# FPGA_I2C.net
KiCad netlist of a schematic drawn in Altium Designer
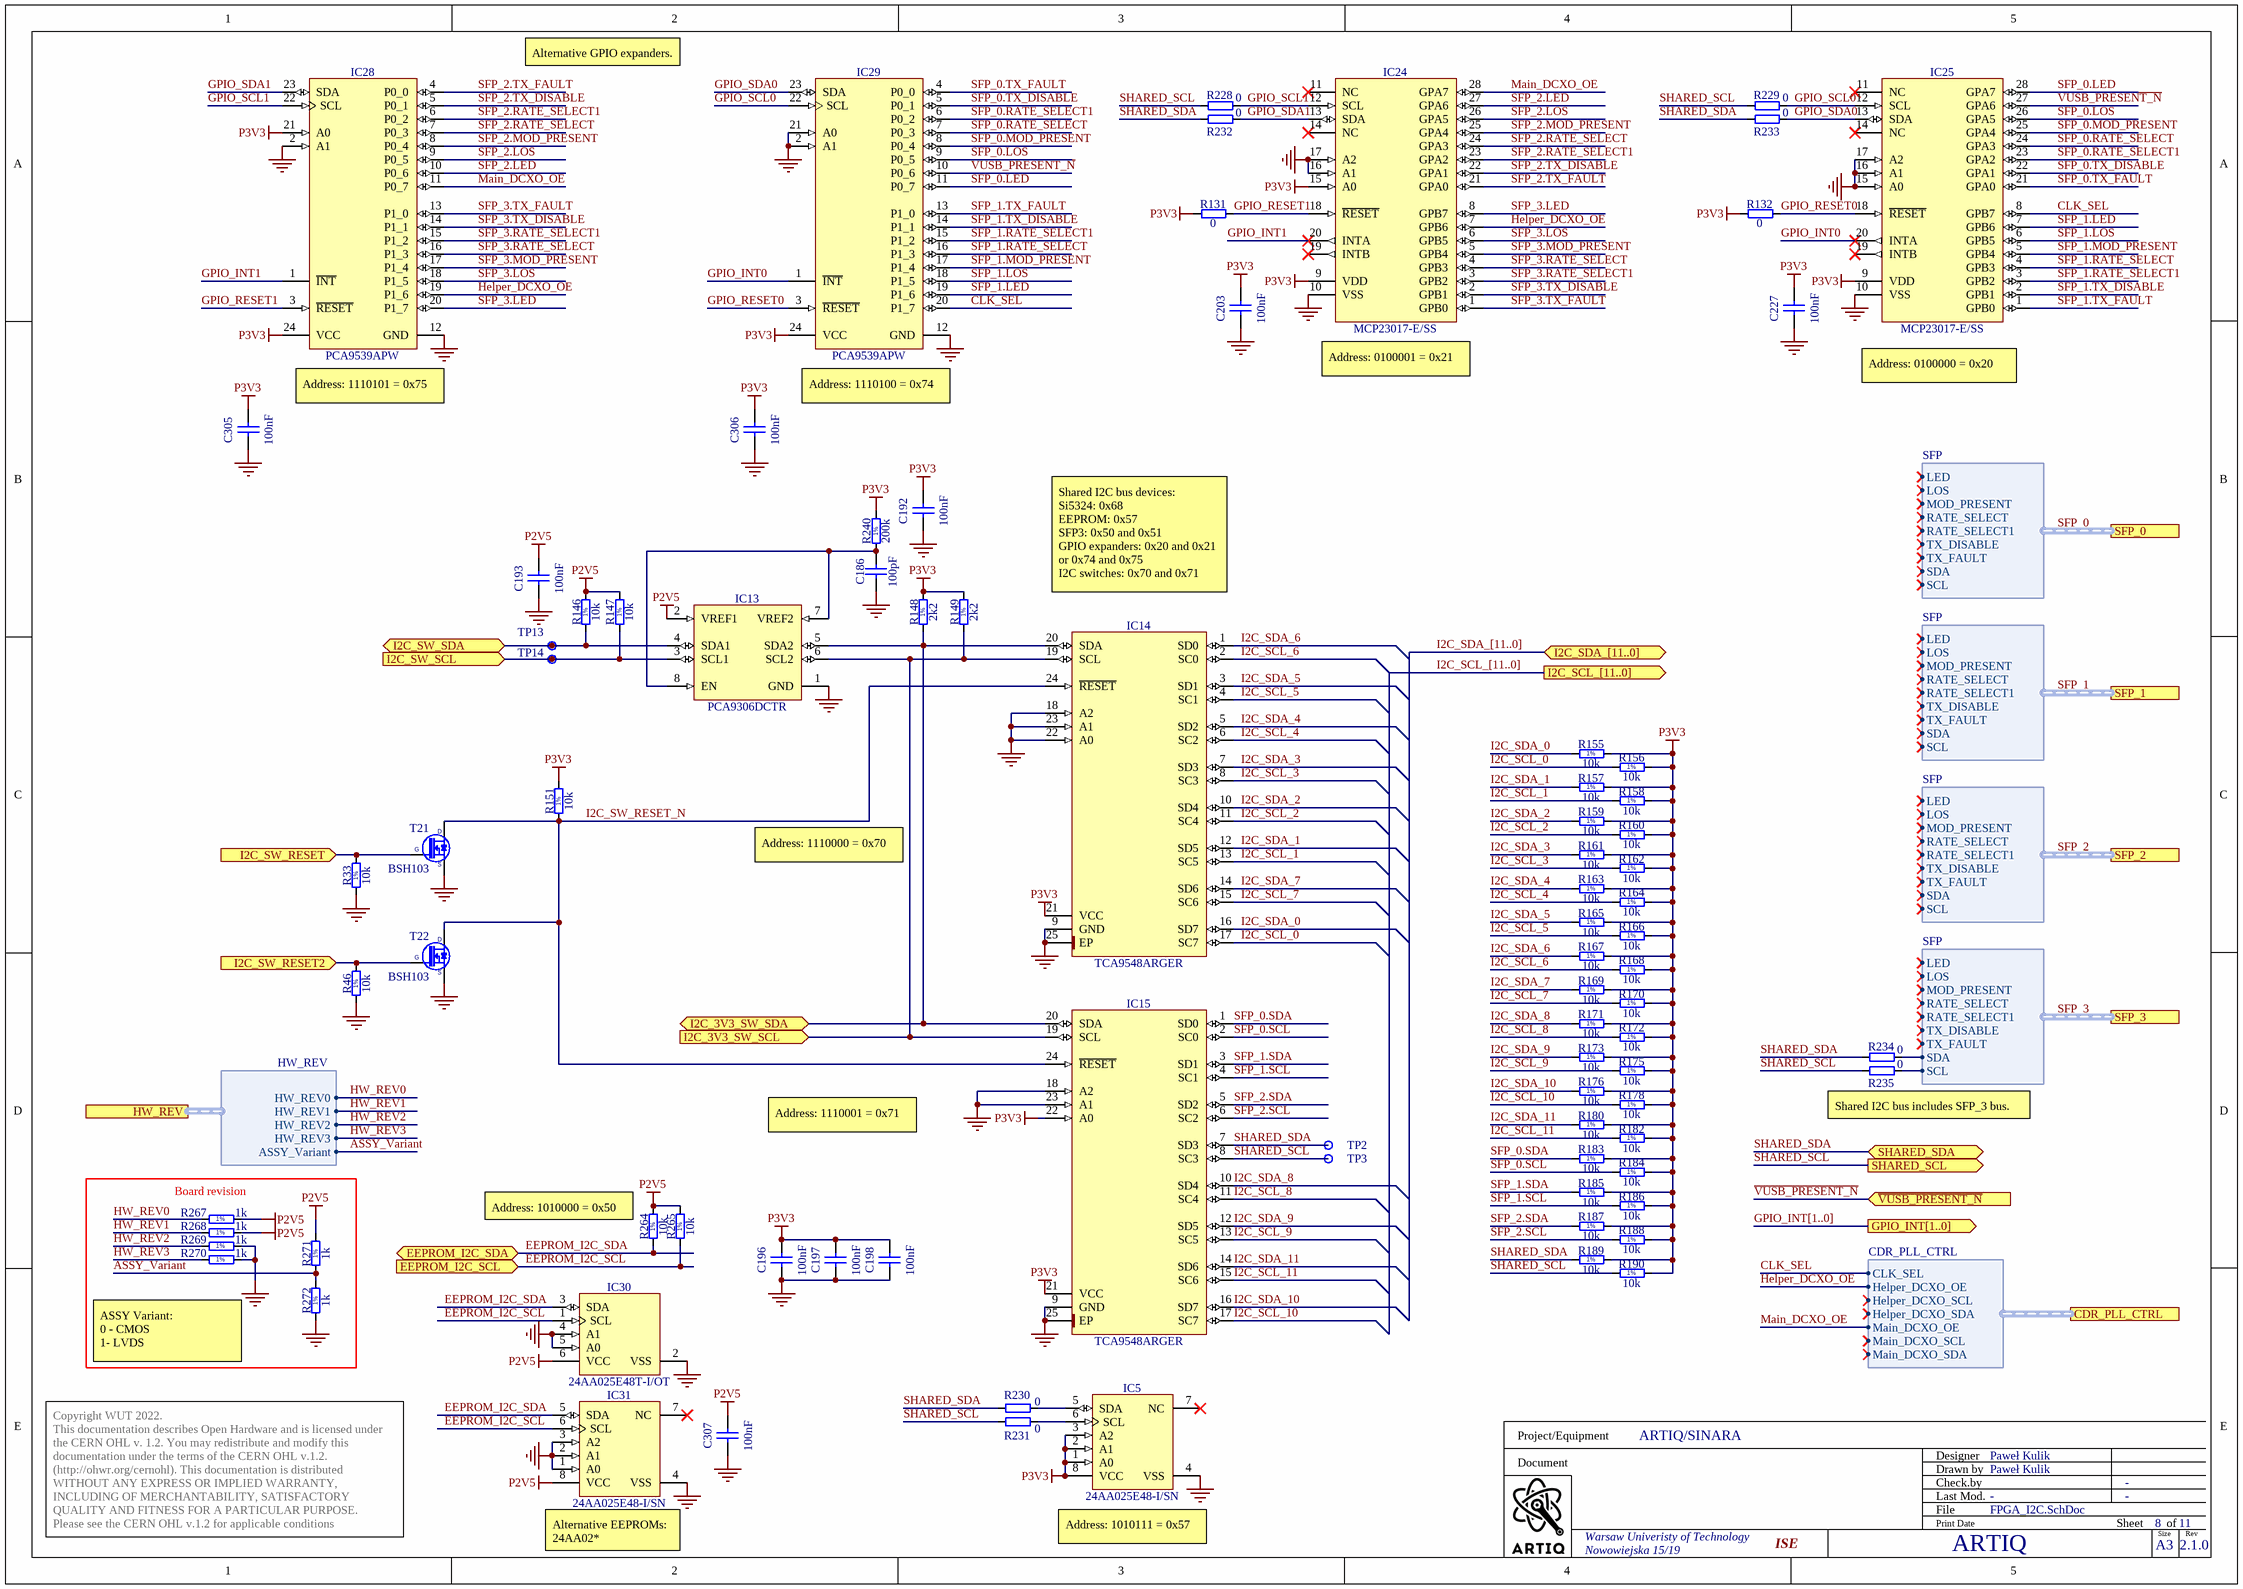
[diagram p0: FPGA_I2C.SchDoc]

(export (version "E")
  (design (tool "Eeschema 10.0.6"))
  (components
    (comp (ref "C186")
      (value "100pF")
      (footprint "CAPC1005X55N")
      (description "Non-polarised capacitor")
      (fields
        (field (name "PART NUMBER") "CC0402_100PF_50V_5%_C0G")
        (field (name "VOLTAGE") "50V")
        (field (name "AUTHOR") "CERN DEM JLC")
      )
      (libsource (lib "Capacitors") (part "Capacitor - non polarized"))
    )
    (comp (ref "C192")
      (value "100nF")
      (footprint "CAPC0603X33N")
      (description "Non-polarised capacitor")
      (fields
        (field (name "PART NUMBER") "CC0201_100NF_6.3V_10%_X5R")
        (field (name "VOLTAGE") "6.3V")
        (field (name "AUTHOR") "CERN DEM JLC")
      )
      (libsource (lib "Capacitors") (part "Capacitor - non polarized"))
    )
    (comp (ref "C193")
      (value "100nF")
      (footprint "CAPC0603X33N")
      (description "Non-polarised capacitor")
      (fields
        (field (name "PART NUMBER") "CC0201_100NF_6.3V_10%_X5R")
        (field (name "VOLTAGE") "6.3V")
        (field (name "AUTHOR") "CERN DEM JLC")
      )
      (libsource (lib "Capacitors") (part "Capacitor - non polarized"))
    )
    (comp (ref "C196")
      (value "100nF")
      (footprint "CAPC0603X33N")
      (description "Non-polarised capacitor")
      (fields
        (field (name "PART NUMBER") "CC0201_100NF_6.3V_10%_X5R")
        (field (name "VOLTAGE") "6.3V")
        (field (name "AUTHOR") "CERN DEM JLC")
      )
      (libsource (lib "Capacitors") (part "Capacitor - non polarized"))
    )
    (comp (ref "C197")
      (value "100nF")
      (footprint "CAPC0603X33N")
      (description "Non-polarised capacitor")
      (fields
        (field (name "PART NUMBER") "CC0201_100NF_6.3V_10%_X5R")
        (field (name "VOLTAGE") "6.3V")
        (field (name "AUTHOR") "CERN DEM JLC")
      )
      (libsource (lib "Capacitors") (part "Capacitor - non polarized"))
    )
    (comp (ref "C198")
      (value "100nF")
      (footprint "CAPC0603X33N")
      (description "Non-polarised capacitor")
      (fields
        (field (name "PART NUMBER") "CC0201_100NF_6.3V_10%_X5R")
        (field (name "VOLTAGE") "6.3V")
        (field (name "AUTHOR") "CERN DEM JLC")
      )
      (libsource (lib "Capacitors") (part "Capacitor - non polarized"))
    )
    (comp (ref "C203")
      (value "100nF")
      (footprint "CAPC0603X33N")
      (description "Non-polarised capacitor")
      (fields
        (field (name "PART NUMBER") "CC0201_100NF_6.3V_10%_X5R")
        (field (name "VOLTAGE") "6.3V")
        (field (name "AUTHOR") "CERN DEM JLC")
      )
      (libsource (lib "Capacitors") (part "Capacitor - non polarized"))
    )
    (comp (ref "C227")
      (value "100nF")
      (footprint "CAPC0603X33N")
      (description "Non-polarised capacitor")
      (fields
        (field (name "PART NUMBER") "CC0201_100NF_6.3V_10%_X5R")
        (field (name "VOLTAGE") "6.3V")
        (field (name "AUTHOR") "CERN DEM JLC")
      )
      (libsource (lib "Capacitors") (part "Capacitor - non polarized"))
    )
    (comp (ref "C305")
      (value "100nF")
      (footprint "CAPC0603X33N")
      (description "Non-polarised capacitor")
      (fields
        (field (name "PART NUMBER") "CC0201_100NF_6.3V_10%_X5R")
        (field (name "VOLTAGE") "6.3V")
        (field (name "AUTHOR") "CERN DEM JLC")
      )
      (libsource (lib "Capacitors") (part "Capacitor - non polarized"))
    )
    (comp (ref "C306")
      (value "100nF")
      (footprint "CAPC0603X33N")
      (description "Non-polarised capacitor")
      (fields
        (field (name "PART NUMBER") "CC0201_100NF_6.3V_10%_X5R")
        (field (name "VOLTAGE") "6.3V")
        (field (name "AUTHOR") "CERN DEM JLC")
      )
      (libsource (lib "Capacitors") (part "Capacitor - non polarized"))
    )
    (comp (ref "C307")
      (value "100nF")
      (footprint "CAPC1005X55N")
      (description "Non-polarised capacitor")
      (fields
        (field (name "PART NUMBER") "CC0402_100NF_16V_10%_X5R")
        (field (name "VOLTAGE") "16V")
        (field (name "AUTHOR") "CERN DEM JLC")
      )
      (libsource (lib "Capacitors") (part "Capacitor - non polarized"))
    )
    (comp (ref "IC5")
      (value "24AA025E48-I/SN")
      (footprint "SOIC127P600X175-8N")
      (description "1.7V-5.5V, 2K I2C™ Serial EEPROMs with EUI-48™ Node Identity")
      (fields (field (name "MANUFACTURER") "MICROCHIP TECHNOLOGY") (field (name "AUTHOR") "CERN DEM MR"))
      (libsource (lib "ICs And Semiconductors") (part "24AA025E48-I/SN"))
    )
    (comp (ref "IC13")
      (value "PCA9306DCTR")
      (footprint "SOP65P400X130-8N")
      (description "Dual Bidirectional I2C Bus And SMBus Voltage-Level Translator")
      (fields (field (name "MANUFACTURER") "TEXAS INSTRUMENTS") (field (name "AUTHOR") "CERN DEM JLC"))
      (libsource (lib "ICs And Semiconductors") (part "PCA9306D"))
    )
    (comp (ref "IC14")
      (value "TCA9548ARGER")
      (footprint "QFN50P400X400X100-25N-S220")
      (description "Low Voltage 8-Channel I2C Switch With Reset")
      (fields (field (name "MANUFACTURER") "TEXAS INSTRUMENTS") (field (name "AUTHOR") "CERN DEM JLC"))
      (libsource (lib "ICs And Semiconductors") (part "TCA9548ARGER"))
    )
    (comp (ref "IC15")
      (value "TCA9548ARGER")
      (footprint "QFN50P400X400X100-25N-S220")
      (description "Low Voltage 8-Channel I2C Switch With Reset")
      (fields (field (name "MANUFACTURER") "TEXAS INSTRUMENTS") (field (name "AUTHOR") "CERN DEM JLC"))
      (libsource (lib "ICs And Semiconductors") (part "TCA9548ARGER"))
    )
    (comp (ref "IC24")
      (value "MCP23017-E/SS")
      (footprint "SOP65P780X200-28N")
      (description "16-bit I/O Port Expander With Serial Interface")
      (fields (field (name "MANUFACTURER") "MICROCHIP TECHNOLOGY") (field (name "AUTHOR") "CERN DEM JLC"))
      (libsource (lib "ICs And Semiconductors") (part "MCP23017-E/SS"))
    )
    (comp (ref "IC25")
      (value "MCP23017-E/SS")
      (footprint "SOP65P780X200-28N")
      (description "16-bit I/O Port Expander With Serial Interface")
      (fields (field (name "MANUFACTURER") "MICROCHIP TECHNOLOGY") (field (name "AUTHOR") "CERN DEM JLC"))
      (libsource (lib "ICs And Semiconductors") (part "MCP23017-E/SS"))
    )
    (comp (ref "IC28")
      (value "PCA9539APW")
      (footprint "SOP65P640X110-24N")
      (description "Low-Voltage 16-Bit I2C-Bus I/O Port with Interrupt and Reset")
      (fields (field (name "MANUFACTURER") "NXP SEMICONDUCTORS") (field (name "AUTHOR") "CERN DEM JMW"))
      (libsource (lib "ICs And Semiconductors") (part "PCA9539APW"))
    )
    (comp (ref "IC29")
      (value "PCA9539APW")
      (footprint "SOP65P640X110-24N")
      (description "Low-Voltage 16-Bit I2C-Bus I/O Port with Interrupt and Reset")
      (fields (field (name "MANUFACTURER") "NXP SEMICONDUCTORS") (field (name "AUTHOR") "CERN DEM JMW"))
      (libsource (lib "ICs And Semiconductors") (part "PCA9539APW"))
    )
    (comp (ref "IC30")
      (value "24AA025E48T-I/OT")
      (footprint "SOT95P280X145-6N")
      (description "1.7V-5.5V, 2K I2C Serial EEPROM With EUI-48 Node Identity")
      (fields (field (name "MANUFACTURER") "MICROCHIP TECHNOLOGY") (field (name "AUTHOR") "CERN DEM BC"))
      (libsource (lib "ICs And Semiconductors") (part "24AA025E48T-I/OT"))
    )
    (comp (ref "IC31")
      (value "24AA025E48-I/SN")
      (footprint "SOIC127P600X175-8N")
      (description "1.7V-5.5V, 2K I2C™ Serial EEPROMs with EUI-48™ Node Identity")
      (fields (field (name "MANUFACTURER") "MICROCHIP TECHNOLOGY") (field (name "AUTHOR") "CERN DEM MR"))
      (libsource (lib "ICs And Semiconductors") (part "24AA025E48-I/SN"))
    )
    (comp (ref "R33")
      (value "10k")
      (footprint "RESC1005X40N")
      (description "Resistor - 1%")
      (fields
        (field (name "PART NUMBER") "R0402_10K_1%_0.0625W_100PPM")
        (field (name "POWER") "0.0625W")
        (field (name "AUTHOR") "CERN DEM JLC")
      )
      (libsource (lib "Resistors") (part "Resistor - 1%"))
    )
    (comp (ref "R46")
      (value "10k")
      (footprint "RESC1005X40N")
      (description "Resistor - 1%")
      (fields
        (field (name "PART NUMBER") "R0402_10K_1%_0.0625W_100PPM")
        (field (name "POWER") "0.0625W")
        (field (name "AUTHOR") "CERN DEM JLC")
      )
      (libsource (lib "Resistors") (part "Resistor - 1%"))
    )
    (comp (ref "R131")
      (value "0")
      (footprint "RESC1005X40N")
      (description "Resistor")
      (fields
        (field (name "PART NUMBER") "R0402_0R_JUMPER")
        (field (name "MANUFACTURER") "GENERIC")
        (field (name "AUTHOR") "CERN DEM JLC")
      )
      (libsource (lib "Resistors") (part "Resistor"))
    )
    (comp (ref "R132")
      (value "0")
      (footprint "RESC1005X40N")
      (description "Resistor")
      (fields
        (field (name "PART NUMBER") "R0402_0R_JUMPER")
        (field (name "MANUFACTURER") "GENERIC")
        (field (name "AUTHOR") "CERN DEM JLC")
      )
      (libsource (lib "Resistors") (part "Resistor"))
    )
    (comp (ref "R146")
      (value "10k")
      (footprint "RESC1005X40N")
      (description "Resistor - 1%")
      (fields
        (field (name "PART NUMBER") "R0402_10K_1%_0.0625W_100PPM")
        (field (name "POWER") "0.0625W")
        (field (name "AUTHOR") "CERN DEM JLC")
      )
      (libsource (lib "Resistors") (part "Resistor - 1%"))
    )
    (comp (ref "R147")
      (value "10k")
      (footprint "RESC1005X40N")
      (description "Resistor - 1%")
      (fields
        (field (name "PART NUMBER") "R0402_10K_1%_0.0625W_100PPM")
        (field (name "POWER") "0.0625W")
        (field (name "AUTHOR") "CERN DEM JLC")
      )
      (libsource (lib "Resistors") (part "Resistor - 1%"))
    )
    (comp (ref "R148")
      (value "2k2")
      (footprint "RESC1005X40N")
      (description "Resistor - 1%")
      (fields
        (field (name "PART NUMBER") "R0402_2K2_1%_0.0625W_100PPM")
        (field (name "POWER") "0.0625W")
        (field (name "AUTHOR") "CERN DEM JLC")
      )
      (libsource (lib "Resistors") (part "Resistor - 1%"))
    )
    (comp (ref "R149")
      (value "2k2")
      (footprint "RESC1005X40N")
      (description "Resistor - 1%")
      (fields
        (field (name "PART NUMBER") "R0402_2K2_1%_0.0625W_100PPM")
        (field (name "POWER") "0.0625W")
        (field (name "AUTHOR") "CERN DEM JLC")
      )
      (libsource (lib "Resistors") (part "Resistor - 1%"))
    )
    (comp (ref "R151")
      (value "10k")
      (footprint "RESC1005X40N")
      (description "Resistor - 1%")
      (fields
        (field (name "PART NUMBER") "R0402_10K_1%_0.0625W_100PPM")
        (field (name "POWER") "0.0625W")
        (field (name "AUTHOR") "CERN DEM JLC")
      )
      (libsource (lib "Resistors") (part "Resistor - 1%"))
    )
    (comp (ref "R155")
      (value "10k")
      (footprint "RESC1005X40N")
      (description "Resistor - 1%")
      (fields
        (field (name "PART NUMBER") "R0402_10K_1%_0.0625W_100PPM")
        (field (name "POWER") "0.0625W")
        (field (name "AUTHOR") "CERN DEM JLC")
      )
      (libsource (lib "Resistors") (part "Resistor - 1%"))
    )
    (comp (ref "R156")
      (value "10k")
      (footprint "RESC1005X40N")
      (description "Resistor - 1%")
      (fields
        (field (name "PART NUMBER") "R0402_10K_1%_0.0625W_100PPM")
        (field (name "POWER") "0.0625W")
        (field (name "AUTHOR") "CERN DEM JLC")
      )
      (libsource (lib "Resistors") (part "Resistor - 1%"))
    )
    (comp (ref "R157")
      (value "10k")
      (footprint "RESC1005X40N")
      (description "Resistor - 1%")
      (fields
        (field (name "PART NUMBER") "R0402_10K_1%_0.0625W_100PPM")
        (field (name "POWER") "0.0625W")
        (field (name "AUTHOR") "CERN DEM JLC")
      )
      (libsource (lib "Resistors") (part "Resistor - 1%"))
    )
    (comp (ref "R158")
      (value "10k")
      (footprint "RESC1005X40N")
      (description "Resistor - 1%")
      (fields
        (field (name "PART NUMBER") "R0402_10K_1%_0.0625W_100PPM")
        (field (name "POWER") "0.0625W")
        (field (name "AUTHOR") "CERN DEM JLC")
      )
      (libsource (lib "Resistors") (part "Resistor - 1%"))
    )
    (comp (ref "R159")
      (value "10k")
      (footprint "RESC1005X40N")
      (description "Resistor - 1%")
      (fields
        (field (name "PART NUMBER") "R0402_10K_1%_0.0625W_100PPM")
        (field (name "POWER") "0.0625W")
        (field (name "AUTHOR") "CERN DEM JLC")
      )
      (libsource (lib "Resistors") (part "Resistor - 1%"))
    )
    (comp (ref "R160")
      (value "10k")
      (footprint "RESC1005X40N")
      (description "Resistor - 1%")
      (fields
        (field (name "PART NUMBER") "R0402_10K_1%_0.0625W_100PPM")
        (field (name "POWER") "0.0625W")
        (field (name "AUTHOR") "CERN DEM JLC")
      )
      (libsource (lib "Resistors") (part "Resistor - 1%"))
    )
    (comp (ref "R161")
      (value "10k")
      (footprint "RESC1005X40N")
      (description "Resistor - 1%")
      (fields
        (field (name "PART NUMBER") "R0402_10K_1%_0.0625W_100PPM")
        (field (name "POWER") "0.0625W")
        (field (name "AUTHOR") "CERN DEM JLC")
      )
      (libsource (lib "Resistors") (part "Resistor - 1%"))
    )
    (comp (ref "R162")
      (value "10k")
      (footprint "RESC1005X40N")
      (description "Resistor - 1%")
      (fields
        (field (name "PART NUMBER") "R0402_10K_1%_0.0625W_100PPM")
        (field (name "POWER") "0.0625W")
        (field (name "AUTHOR") "CERN DEM JLC")
      )
      (libsource (lib "Resistors") (part "Resistor - 1%"))
    )
    (comp (ref "R163")
      (value "10k")
      (footprint "RESC1005X40N")
      (description "Resistor - 1%")
      (fields
        (field (name "PART NUMBER") "R0402_10K_1%_0.0625W_100PPM")
        (field (name "POWER") "0.0625W")
        (field (name "AUTHOR") "CERN DEM JLC")
      )
      (libsource (lib "Resistors") (part "Resistor - 1%"))
    )
    (comp (ref "R164")
      (value "10k")
      (footprint "RESC1005X40N")
      (description "Resistor - 1%")
      (fields
        (field (name "PART NUMBER") "R0402_10K_1%_0.0625W_100PPM")
        (field (name "POWER") "0.0625W")
        (field (name "AUTHOR") "CERN DEM JLC")
      )
      (libsource (lib "Resistors") (part "Resistor - 1%"))
    )
    (comp (ref "R165")
      (value "10k")
      (footprint "RESC1005X40N")
      (description "Resistor - 1%")
      (fields
        (field (name "PART NUMBER") "R0402_10K_1%_0.0625W_100PPM")
        (field (name "POWER") "0.0625W")
        (field (name "AUTHOR") "CERN DEM JLC")
      )
      (libsource (lib "Resistors") (part "Resistor - 1%"))
    )
    (comp (ref "R166")
      (value "10k")
      (footprint "RESC1005X40N")
      (description "Resistor - 1%")
      (fields
        (field (name "PART NUMBER") "R0402_10K_1%_0.0625W_100PPM")
        (field (name "POWER") "0.0625W")
        (field (name "AUTHOR") "CERN DEM JLC")
      )
      (libsource (lib "Resistors") (part "Resistor - 1%"))
    )
    (comp (ref "R167")
      (value "10k")
      (footprint "RESC1005X40N")
      (description "Resistor - 1%")
      (fields
        (field (name "PART NUMBER") "R0402_10K_1%_0.0625W_100PPM")
        (field (name "POWER") "0.0625W")
        (field (name "AUTHOR") "CERN DEM JLC")
      )
      (libsource (lib "Resistors") (part "Resistor - 1%"))
    )
    (comp (ref "R168")
      (value "10k")
      (footprint "RESC1005X40N")
      (description "Resistor - 1%")
      (fields
        (field (name "PART NUMBER") "R0402_10K_1%_0.0625W_100PPM")
        (field (name "POWER") "0.0625W")
        (field (name "AUTHOR") "CERN DEM JLC")
      )
      (libsource (lib "Resistors") (part "Resistor - 1%"))
    )
    (comp (ref "R169")
      (value "10k")
      (footprint "RESC1005X40N")
      (description "Resistor - 1%")
      (fields
        (field (name "PART NUMBER") "R0402_10K_1%_0.0625W_100PPM")
        (field (name "POWER") "0.0625W")
        (field (name "AUTHOR") "CERN DEM JLC")
      )
      (libsource (lib "Resistors") (part "Resistor - 1%"))
    )
    (comp (ref "R170")
      (value "10k")
      (footprint "RESC1005X40N")
      (description "Resistor - 1%")
      (fields
        (field (name "PART NUMBER") "R0402_10K_1%_0.0625W_100PPM")
        (field (name "POWER") "0.0625W")
        (field (name "AUTHOR") "CERN DEM JLC")
      )
      (libsource (lib "Resistors") (part "Resistor - 1%"))
    )
    (comp (ref "R171")
      (value "10k")
      (footprint "RESC1005X40N")
      (description "Resistor - 1%")
      (fields
        (field (name "PART NUMBER") "R0402_10K_1%_0.0625W_100PPM")
        (field (name "POWER") "0.0625W")
        (field (name "AUTHOR") "CERN DEM JLC")
      )
      (libsource (lib "Resistors") (part "Resistor - 1%"))
    )
    (comp (ref "R172")
      (value "10k")
      (footprint "RESC1005X40N")
      (description "Resistor - 1%")
      (fields
        (field (name "PART NUMBER") "R0402_10K_1%_0.0625W_100PPM")
        (field (name "POWER") "0.0625W")
        (field (name "AUTHOR") "CERN DEM JLC")
      )
      (libsource (lib "Resistors") (part "Resistor - 1%"))
    )
    (comp (ref "R173")
      (value "10k")
      (footprint "RESC1005X40N")
      (description "Resistor - 1%")
      (fields
        (field (name "PART NUMBER") "R0402_10K_1%_0.0625W_100PPM")
        (field (name "POWER") "0.0625W")
        (field (name "AUTHOR") "CERN DEM JLC")
      )
      (libsource (lib "Resistors") (part "Resistor - 1%"))
    )
    (comp (ref "R175")
      (value "10k")
      (footprint "RESC1005X40N")
      (description "Resistor - 1%")
      (fields
        (field (name "PART NUMBER") "R0402_10K_1%_0.0625W_100PPM")
        (field (name "POWER") "0.0625W")
        (field (name "AUTHOR") "CERN DEM JLC")
      )
      (libsource (lib "Resistors") (part "Resistor - 1%"))
    )
    (comp (ref "R176")
      (value "10k")
      (footprint "RESC1005X40N")
      (description "Resistor - 1%")
      (fields
        (field (name "PART NUMBER") "R0402_10K_1%_0.0625W_100PPM")
        (field (name "POWER") "0.0625W")
        (field (name "AUTHOR") "CERN DEM JLC")
      )
      (libsource (lib "Resistors") (part "Resistor - 1%"))
    )
    (comp (ref "R178")
      (value "10k")
      (footprint "RESC1005X40N")
      (description "Resistor - 1%")
      (fields
        (field (name "PART NUMBER") "R0402_10K_1%_0.0625W_100PPM")
        (field (name "POWER") "0.0625W")
        (field (name "AUTHOR") "CERN DEM JLC")
      )
      (libsource (lib "Resistors") (part "Resistor - 1%"))
    )
    (comp (ref "R180")
      (value "10k")
      (footprint "RESC1005X40N")
      (description "Resistor - 1%")
      (fields
        (field (name "PART NUMBER") "R0402_10K_1%_0.0625W_100PPM")
        (field (name "POWER") "0.0625W")
        (field (name "AUTHOR") "CERN DEM JLC")
      )
      (libsource (lib "Resistors") (part "Resistor - 1%"))
    )
    (comp (ref "R182")
      (value "10k")
      (footprint "RESC1005X40N")
      (description "Resistor - 1%")
      (fields
        (field (name "PART NUMBER") "R0402_10K_1%_0.0625W_100PPM")
        (field (name "POWER") "0.0625W")
        (field (name "AUTHOR") "CERN DEM JLC")
      )
      (libsource (lib "Resistors") (part "Resistor - 1%"))
    )
    (comp (ref "R183")
      (value "10k")
      (footprint "RESC1005X40N")
      (description "Resistor - 1%")
      (fields
        (field (name "PART NUMBER") "R0402_10K_1%_0.0625W_100PPM")
        (field (name "POWER") "0.0625W")
        (field (name "AUTHOR") "CERN DEM JLC")
      )
      (libsource (lib "Resistors") (part "Resistor - 1%"))
    )
    (comp (ref "R184")
      (value "10k")
      (footprint "RESC1005X40N")
      (description "Resistor - 1%")
      (fields
        (field (name "PART NUMBER") "R0402_10K_1%_0.0625W_100PPM")
        (field (name "POWER") "0.0625W")
        (field (name "AUTHOR") "CERN DEM JLC")
      )
      (libsource (lib "Resistors") (part "Resistor - 1%"))
    )
    (comp (ref "R185")
      (value "10k")
      (footprint "RESC1005X40N")
      (description "Resistor - 1%")
      (fields
        (field (name "PART NUMBER") "R0402_10K_1%_0.0625W_100PPM")
        (field (name "POWER") "0.0625W")
        (field (name "AUTHOR") "CERN DEM JLC")
      )
      (libsource (lib "Resistors") (part "Resistor - 1%"))
    )
    (comp (ref "R186")
      (value "10k")
      (footprint "RESC1005X40N")
      (description "Resistor - 1%")
      (fields
        (field (name "PART NUMBER") "R0402_10K_1%_0.0625W_100PPM")
        (field (name "POWER") "0.0625W")
        (field (name "AUTHOR") "CERN DEM JLC")
      )
      (libsource (lib "Resistors") (part "Resistor - 1%"))
    )
    (comp (ref "R187")
      (value "10k")
      (footprint "RESC1005X40N")
      (description "Resistor - 1%")
      (fields
        (field (name "PART NUMBER") "R0402_10K_1%_0.0625W_100PPM")
        (field (name "POWER") "0.0625W")
        (field (name "AUTHOR") "CERN DEM JLC")
      )
      (libsource (lib "Resistors") (part "Resistor - 1%"))
    )
    (comp (ref "R188")
      (value "10k")
      (footprint "RESC1005X40N")
      (description "Resistor - 1%")
      (fields
        (field (name "PART NUMBER") "R0402_10K_1%_0.0625W_100PPM")
        (field (name "POWER") "0.0625W")
        (field (name "AUTHOR") "CERN DEM JLC")
      )
      (libsource (lib "Resistors") (part "Resistor - 1%"))
    )
    (comp (ref "R189")
      (value "10k")
      (footprint "RESC1005X40N")
      (description "Resistor - 1%")
      (fields
        (field (name "PART NUMBER") "R0402_10K_1%_0.0625W_100PPM")
        (field (name "POWER") "0.0625W")
        (field (name "AUTHOR") "CERN DEM JLC")
      )
      (libsource (lib "Resistors") (part "Resistor - 1%"))
    )
    (comp (ref "R190")
      (value "10k")
      (footprint "RESC1005X40N")
      (description "Resistor - 1%")
      (fields
        (field (name "PART NUMBER") "R0402_10K_1%_0.0625W_100PPM")
        (field (name "POWER") "0.0625W")
        (field (name "AUTHOR") "CERN DEM JLC")
      )
      (libsource (lib "Resistors") (part "Resistor - 1%"))
    )
    (comp (ref "R228")
      (value "0")
      (footprint "RESC1005X40N")
      (description "Resistor")
      (fields
        (field (name "PART NUMBER") "R0402_0R_JUMPER")
        (field (name "MANUFACTURER") "GENERIC")
        (field (name "AUTHOR") "CERN DEM JLC")
      )
      (libsource (lib "Resistors") (part "Resistor"))
    )
    (comp (ref "R229")
      (value "0")
      (footprint "RESC1005X40N")
      (description "Resistor")
      (fields
        (field (name "PART NUMBER") "R0402_0R_JUMPER")
        (field (name "MANUFACTURER") "GENERIC")
        (field (name "AUTHOR") "CERN DEM JLC")
      )
      (libsource (lib "Resistors") (part "Resistor"))
    )
    (comp (ref "R230")
      (value "0")
      (footprint "RESC1005X40N")
      (description "Resistor")
      (fields
        (field (name "PART NUMBER") "R0402_0R_JUMPER")
        (field (name "MANUFACTURER") "GENERIC")
        (field (name "AUTHOR") "CERN DEM JLC")
      )
      (libsource (lib "Resistors") (part "Resistor"))
    )
    (comp (ref "R231")
      (value "0")
      (footprint "RESC1005X40N")
      (description "Resistor")
      (fields
        (field (name "PART NUMBER") "R0402_0R_JUMPER")
        (field (name "MANUFACTURER") "GENERIC")
        (field (name "AUTHOR") "CERN DEM JLC")
      )
      (libsource (lib "Resistors") (part "Resistor"))
    )
    (comp (ref "R232")
      (value "0")
      (footprint "RESC1005X40N")
      (description "Resistor")
      (fields
        (field (name "PART NUMBER") "R0402_0R_JUMPER")
        (field (name "MANUFACTURER") "GENERIC")
        (field (name "AUTHOR") "CERN DEM JLC")
      )
      (libsource (lib "Resistors") (part "Resistor"))
    )
    (comp (ref "R233")
      (value "0")
      (footprint "RESC1005X40N")
      (description "Resistor")
      (fields
        (field (name "PART NUMBER") "R0402_0R_JUMPER")
        (field (name "MANUFACTURER") "GENERIC")
        (field (name "AUTHOR") "CERN DEM JLC")
      )
      (libsource (lib "Resistors") (part "Resistor"))
    )
    (comp (ref "R234")
      (value "0")
      (footprint "RESC1005X40N")
      (description "Resistor")
      (fields
        (field (name "PART NUMBER") "R0402_0R_JUMPER")
        (field (name "MANUFACTURER") "GENERIC")
        (field (name "AUTHOR") "CERN DEM JLC")
      )
      (libsource (lib "Resistors") (part "Resistor"))
    )
    (comp (ref "R235")
      (value "0")
      (footprint "RESC1005X40N")
      (description "Resistor")
      (fields
        (field (name "PART NUMBER") "R0402_0R_JUMPER")
        (field (name "MANUFACTURER") "GENERIC")
        (field (name "AUTHOR") "CERN DEM JLC")
      )
      (libsource (lib "Resistors") (part "Resistor"))
    )
    (comp (ref "R240")
      (value "200k")
      (footprint "RESC1005X40N")
      (description "Resistor - 1%")
      (fields
        (field (name "PART NUMBER") "R0402_200K_1%_0.0625W_100PPM")
        (field (name "POWER") "0.0625W")
        (field (name "AUTHOR") "CERN DEM JLC")
      )
      (libsource (lib "Resistors") (part "Resistor - 1%"))
    )
    (comp (ref "R264")
      (value "10k")
      (footprint "RESC1005X40N")
      (description "Resistor - 1%")
      (fields
        (field (name "PART NUMBER") "R0402_10K_1%_0.0625W_100PPM")
        (field (name "POWER") "0.0625W")
        (field (name "AUTHOR") "CERN DEM JLC")
      )
      (libsource (lib "Resistors") (part "Resistor - 1%"))
    )
    (comp (ref "R265")
      (value "10k")
      (footprint "RESC1005X40N")
      (description "Resistor - 1%")
      (fields
        (field (name "PART NUMBER") "R0402_10K_1%_0.0625W_100PPM")
        (field (name "POWER") "0.0625W")
        (field (name "AUTHOR") "CERN DEM JLC")
      )
      (libsource (lib "Resistors") (part "Resistor - 1%"))
    )
    (comp (ref "R267")
      (value "1k")
      (footprint "RESC1005X40N")
      (description "Resistor - 1%")
      (fields
        (field (name "PART NUMBER") "R0402_1K_1%_0.0625W_100PPM")
        (field (name "POWER") "0.0625W")
        (field (name "AUTHOR") "CERN DEM JLC")
      )
      (libsource (lib "Resistors") (part "Resistor - 1%"))
    )
    (comp (ref "R268")
      (value "1k")
      (footprint "RESC1005X40N")
      (description "Resistor - 1%")
      (fields
        (field (name "PART NUMBER") "R0402_1K_1%_0.0625W_100PPM")
        (field (name "POWER") "0.0625W")
        (field (name "AUTHOR") "CERN DEM JLC")
      )
      (libsource (lib "Resistors") (part "Resistor - 1%"))
    )
    (comp (ref "R269")
      (value "1k")
      (footprint "RESC1005X40N")
      (description "Resistor - 1%")
      (fields
        (field (name "PART NUMBER") "R0402_1K_1%_0.0625W_100PPM")
        (field (name "POWER") "0.0625W")
        (field (name "AUTHOR") "CERN DEM JLC")
      )
      (libsource (lib "Resistors") (part "Resistor - 1%"))
    )
    (comp (ref "R270")
      (value "1k")
      (footprint "RESC1005X40N")
      (description "Resistor - 1%")
      (fields
        (field (name "PART NUMBER") "R0402_1K_1%_0.0625W_100PPM")
        (field (name "POWER") "0.0625W")
        (field (name "AUTHOR") "CERN DEM JLC")
      )
      (libsource (lib "Resistors") (part "Resistor - 1%"))
    )
    (comp (ref "R271")
      (value "1k")
      (footprint "RESC1005X40N")
      (description "Resistor - 1%")
      (fields
        (field (name "PART NUMBER") "R0402_1K_1%_0.0625W_100PPM")
        (field (name "POWER") "0.0625W")
        (field (name "AUTHOR") "CERN DEM JLC")
      )
      (libsource (lib "Resistors") (part "Resistor - 1%"))
    )
    (comp (ref "R272")
      (value "1k")
      (footprint "RESC1005X40N")
      (description "Resistor - 1%")
      (fields
        (field (name "PART NUMBER") "R0402_1K_1%_0.0625W_100PPM")
        (field (name "POWER") "0.0625W")
        (field (name "AUTHOR") "CERN DEM JLC")
      )
      (libsource (lib "Resistors") (part "Resistor - 1%"))
    )
    (comp (ref "T21")
      (value "BSH103")
      (footprint "SOT95P230X110-3N")
      (description "N-CHANNEL MOSFET WITH DIODE")
      (fields (field (name "MANUFACTURER") "NEXPERIA") (field (name "AUTHOR") "CERN DEM JLC"))
      (libsource (lib "ICs And Semiconductors") (part "N-MOSFET-D 1G 2S 3D"))
    )
    (comp (ref "T22")
      (value "BSH103")
      (footprint "SOT95P230X110-3N")
      (description "N-CHANNEL MOSFET WITH DIODE")
      (fields (field (name "MANUFACTURER") "NEXPERIA") (field (name "AUTHOR") "CERN DEM JLC"))
      (libsource (lib "ICs And Semiconductors") (part "N-MOSFET-D 1G 2S 3D"))
    )
    (comp (ref "TP2")
      (value "Si5324 I2C SDA")
      (footprint "TPS127")
      (description "Test Point")
      (fields (field (name "PART NUMBER") "SMD_PAD_1.27X1.27MM") (field (name "AUTHOR") "CERN DEM JLC"))
      (libsource (lib "Eletro-mechanical") (part "Test Point"))
    )
    (comp (ref "TP3")
      (value "Si5324 I2C SCL")
      (footprint "TPS127")
      (description "Test Point")
      (fields (field (name "PART NUMBER") "SMD_PAD_1.27X1.27MM") (field (name "AUTHOR") "CERN DEM JLC"))
      (libsource (lib "Eletro-mechanical") (part "Test Point"))
    )
    (comp (ref "TP13")
      (value "I2C SW SDA")
      (footprint "TPS127")
      (description "Test Point")
      (fields (field (name "PART NUMBER") "SMD_PAD_1.27X1.27MM") (field (name "AUTHOR") "CERN DEM JLC"))
      (libsource (lib "Eletro-mechanical") (part "Test Point"))
    )
    (comp (ref "TP14")
      (value "I2C SW SCL")
      (footprint "TPS127")
      (description "Test Point")
      (fields (field (name "PART NUMBER") "SMD_PAD_1.27X1.27MM") (field (name "AUTHOR") "CERN DEM JLC"))
      (libsource (lib "Eletro-mechanical") (part "Test Point"))
    )
  )
  (nets
    (net (code "7") (name "/ASSY_Variant") (class "Default")
      (node (ref "R271") (pin "1") (pinfunction "1_1") (pintype "passive"))
      (node (ref "R272") (pin "2") (pinfunction "2_2") (pintype "passive"))
    )
    (net (code "8") (name "/CLK_SEL") (class "Default")
      (node (ref "IC25") (pin "8") (pinfunction "GPB7_8") (pintype "bidirectional"))
      (node (ref "IC29") (pin "20") (pinfunction "P1_7_20") (pintype "bidirectional"))
    )
    (net (code "9") (name "/EEPROM_I2C_SCL") (class "Default")
      (node (ref "IC30") (pin "1") (pinfunction "SCL_1") (pintype "input"))
      (node (ref "IC31") (pin "6") (pinfunction "SCL_6") (pintype "input"))
      (node (ref "R265") (pin "1") (pinfunction "1_1") (pintype "passive"))
    )
    (net (code "10") (name "/EEPROM_I2C_SDA") (class "Default")
      (node (ref "IC30") (pin "3") (pinfunction "SDA_3") (pintype "bidirectional"))
      (node (ref "IC31") (pin "5") (pinfunction "SDA_5") (pintype "bidirectional"))
      (node (ref "R264") (pin "1") (pinfunction "1_1") (pintype "passive"))
    )
    (net (code "11") (name "/GPIO_INT0") (class "Default")
      (node (ref "IC25") (pin "20") (pinfunction "INTA_20") (pintype "output"))
      (node (ref "IC29") (pin "1") (pinfunction "~{INT}_1") (pintype "open_collector"))
    )
    (net (code "12") (name "/GPIO_INT1") (class "Default")
      (node (ref "IC24") (pin "20") (pinfunction "INTA_20") (pintype "output"))
      (node (ref "IC28") (pin "1") (pinfunction "~{INT}_1") (pintype "open_collector"))
    )
    (net (code "14") (name "/GPIO_RESET0") (class "Default")
      (node (ref "IC25") (pin "18") (pinfunction "~{RESET}_18") (pintype "input"))
      (node (ref "IC29") (pin "3") (pinfunction "~{RESET}_3") (pintype "input"))
      (node (ref "R132") (pin "2") (pinfunction "2_2") (pintype "passive"))
    )
    (net (code "15") (name "/GPIO_RESET1") (class "Default")
      (node (ref "IC24") (pin "18") (pinfunction "~{RESET}_18") (pintype "input"))
      (node (ref "IC28") (pin "3") (pinfunction "~{RESET}_3") (pintype "input"))
      (node (ref "R131") (pin "2") (pinfunction "2_2") (pintype "passive"))
    )
    (net (code "16") (name "/GPIO_SCL0") (class "Default")
      (node (ref "IC25") (pin "12") (pinfunction "SCL_12") (pintype "input"))
      (node (ref "IC29") (pin "22") (pinfunction "SCL_22") (pintype "input"))
      (node (ref "R229") (pin "2") (pinfunction "2_2") (pintype "passive"))
    )
    (net (code "17") (name "/GPIO_SCL1") (class "Default")
      (node (ref "IC24") (pin "12") (pinfunction "SCL_12") (pintype "input"))
      (node (ref "IC28") (pin "22") (pinfunction "SCL_22") (pintype "input"))
      (node (ref "R228") (pin "2") (pinfunction "2_2") (pintype "passive"))
    )
    (net (code "18") (name "/GPIO_SDA0") (class "Default")
      (node (ref "IC25") (pin "13") (pinfunction "SDA_13") (pintype "bidirectional"))
      (node (ref "IC29") (pin "23") (pinfunction "SDA_23") (pintype "bidirectional"))
      (node (ref "R233") (pin "2") (pinfunction "2_2") (pintype "passive"))
    )
    (net (code "19") (name "/GPIO_SDA1") (class "Default")
      (node (ref "IC24") (pin "13") (pinfunction "SDA_13") (pintype "bidirectional"))
      (node (ref "IC28") (pin "23") (pinfunction "SDA_23") (pintype "bidirectional"))
      (node (ref "R232") (pin "2") (pinfunction "2_2") (pintype "passive"))
    )
    (net (code "20") (name "/HW_REV0") (class "Default")
      (node (ref "R267") (pin "1") (pinfunction "1_1") (pintype "passive"))
    )
    (net (code "21") (name "/HW_REV1") (class "Default")
      (node (ref "R268") (pin "1") (pinfunction "1_1") (pintype "passive"))
    )
    (net (code "22") (name "/HW_REV2") (class "Default")
      (node (ref "R269") (pin "1") (pinfunction "1_1") (pintype "passive"))
    )
    (net (code "23") (name "/HW_REV3") (class "Default")
      (node (ref "R270") (pin "1") (pinfunction "1_1") (pintype "passive"))
    )
    (net (code "24") (name "/Helper_DCXO_OE") (class "Default")
      (node (ref "IC24") (pin "7") (pinfunction "GPB6_7") (pintype "bidirectional"))
      (node (ref "IC28") (pin "19") (pinfunction "P1_6_19") (pintype "bidirectional"))
    )
    (net (code "25") (name "/I2C_3V3_SW_SCL") (class "Default")
      (node (ref "IC13") (pin "6") (pinfunction "SCL2_6") (pintype "bidirectional"))
      (node (ref "IC14") (pin "19") (pinfunction "SCL_19") (pintype "bidirectional"))
      (node (ref "IC15") (pin "19") (pinfunction "SCL_19") (pintype "bidirectional"))
      (node (ref "R149") (pin "1") (pinfunction "1_1") (pintype "passive"))
    )
    (net (code "26") (name "/I2C_3V3_SW_SDA") (class "Default")
      (node (ref "IC13") (pin "5") (pinfunction "SDA2_5") (pintype "bidirectional"))
      (node (ref "IC14") (pin "20") (pinfunction "SDA_20") (pintype "bidirectional"))
      (node (ref "IC15") (pin "20") (pinfunction "SDA_20") (pintype "bidirectional"))
      (node (ref "R148") (pin "1") (pinfunction "1_1") (pintype "passive"))
    )
    (net (code "27") (name "/I2C_SCL_0") (class "Default")
      (node (ref "IC14") (pin "17") (pinfunction "SC7_17") (pintype "bidirectional"))
      (node (ref "R156") (pin "1") (pinfunction "1_1") (pintype "passive"))
    )
    (net (code "28") (name "/I2C_SCL_1") (class "Default")
      (node (ref "IC14") (pin "13") (pinfunction "SC5_13") (pintype "bidirectional"))
      (node (ref "R158") (pin "1") (pinfunction "1_1") (pintype "passive"))
    )
    (net (code "29") (name "/I2C_SCL_2") (class "Default")
      (node (ref "IC14") (pin "11") (pinfunction "SC4_11") (pintype "bidirectional"))
      (node (ref "R160") (pin "1") (pinfunction "1_1") (pintype "passive"))
    )
    (net (code "30") (name "/I2C_SCL_3") (class "Default")
      (node (ref "IC14") (pin "8") (pinfunction "SC3_8") (pintype "bidirectional"))
      (node (ref "R162") (pin "1") (pinfunction "1_1") (pintype "passive"))
    )
    (net (code "31") (name "/I2C_SCL_4") (class "Default")
      (node (ref "IC14") (pin "6") (pinfunction "SC2_6") (pintype "bidirectional"))
      (node (ref "R164") (pin "1") (pinfunction "1_1") (pintype "passive"))
    )
    (net (code "32") (name "/I2C_SCL_5") (class "Default")
      (node (ref "IC14") (pin "4") (pinfunction "SC1_4") (pintype "bidirectional"))
      (node (ref "R166") (pin "1") (pinfunction "1_1") (pintype "passive"))
    )
    (net (code "33") (name "/I2C_SCL_6") (class "Default")
      (node (ref "IC14") (pin "2") (pinfunction "SC0_2") (pintype "bidirectional"))
      (node (ref "R168") (pin "1") (pinfunction "1_1") (pintype "passive"))
    )
    (net (code "34") (name "/I2C_SCL_7") (class "Default")
      (node (ref "IC14") (pin "15") (pinfunction "SC6_15") (pintype "bidirectional"))
      (node (ref "R170") (pin "1") (pinfunction "1_1") (pintype "passive"))
    )
    (net (code "35") (name "/I2C_SCL_8") (class "Default")
      (node (ref "IC15") (pin "11") (pinfunction "SC4_11") (pintype "bidirectional"))
      (node (ref "R172") (pin "1") (pinfunction "1_1") (pintype "passive"))
    )
    (net (code "36") (name "/I2C_SCL_9") (class "Default")
      (node (ref "IC15") (pin "13") (pinfunction "SC5_13") (pintype "bidirectional"))
      (node (ref "R175") (pin "1") (pinfunction "1_1") (pintype "passive"))
    )
    (net (code "37") (name "/I2C_SCL_10") (class "Default")
      (node (ref "IC15") (pin "17") (pinfunction "SC7_17") (pintype "bidirectional"))
      (node (ref "R178") (pin "1") (pinfunction "1_1") (pintype "passive"))
    )
    (net (code "38") (name "/I2C_SCL_11") (class "Default")
      (node (ref "IC15") (pin "15") (pinfunction "SC6_15") (pintype "bidirectional"))
      (node (ref "R182") (pin "1") (pinfunction "1_1") (pintype "passive"))
    )
    (net (code "40") (name "/I2C_SDA_0") (class "Default")
      (node (ref "IC14") (pin "16") (pinfunction "SD7_16") (pintype "bidirectional"))
      (node (ref "R155") (pin "1") (pinfunction "1_1") (pintype "passive"))
    )
    (net (code "41") (name "/I2C_SDA_1") (class "Default")
      (node (ref "IC14") (pin "12") (pinfunction "SD5_12") (pintype "bidirectional"))
      (node (ref "R157") (pin "1") (pinfunction "1_1") (pintype "passive"))
    )
    (net (code "42") (name "/I2C_SDA_2") (class "Default")
      (node (ref "IC14") (pin "10") (pinfunction "SD4_10") (pintype "bidirectional"))
      (node (ref "R159") (pin "1") (pinfunction "1_1") (pintype "passive"))
    )
    (net (code "43") (name "/I2C_SDA_3") (class "Default")
      (node (ref "IC14") (pin "7") (pinfunction "SD3_7") (pintype "bidirectional"))
      (node (ref "R161") (pin "1") (pinfunction "1_1") (pintype "passive"))
    )
    (net (code "44") (name "/I2C_SDA_4") (class "Default")
      (node (ref "IC14") (pin "5") (pinfunction "SD2_5") (pintype "bidirectional"))
      (node (ref "R163") (pin "1") (pinfunction "1_1") (pintype "passive"))
    )
    (net (code "45") (name "/I2C_SDA_5") (class "Default")
      (node (ref "IC14") (pin "3") (pinfunction "SD1_3") (pintype "bidirectional"))
      (node (ref "R165") (pin "1") (pinfunction "1_1") (pintype "passive"))
    )
    (net (code "46") (name "/I2C_SDA_6") (class "Default")
      (node (ref "IC14") (pin "1") (pinfunction "SD0_1") (pintype "bidirectional"))
      (node (ref "R167") (pin "1") (pinfunction "1_1") (pintype "passive"))
    )
    (net (code "47") (name "/I2C_SDA_7") (class "Default")
      (node (ref "IC14") (pin "14") (pinfunction "SD6_14") (pintype "bidirectional"))
      (node (ref "R169") (pin "1") (pinfunction "1_1") (pintype "passive"))
    )
    (net (code "48") (name "/I2C_SDA_8") (class "Default")
      (node (ref "IC15") (pin "10") (pinfunction "SD4_10") (pintype "bidirectional"))
      (node (ref "R171") (pin "1") (pinfunction "1_1") (pintype "passive"))
    )
    (net (code "49") (name "/I2C_SDA_9") (class "Default")
      (node (ref "IC15") (pin "12") (pinfunction "SD5_12") (pintype "bidirectional"))
      (node (ref "R173") (pin "1") (pinfunction "1_1") (pintype "passive"))
    )
    (net (code "50") (name "/I2C_SDA_10") (class "Default")
      (node (ref "IC15") (pin "16") (pinfunction "SD7_16") (pintype "bidirectional"))
      (node (ref "R176") (pin "1") (pinfunction "1_1") (pintype "passive"))
    )
    (net (code "51") (name "/I2C_SDA_11") (class "Default")
      (node (ref "IC15") (pin "14") (pinfunction "SD6_14") (pintype "bidirectional"))
      (node (ref "R180") (pin "1") (pinfunction "1_1") (pintype "passive"))
    )
    (net (code "53") (name "/I2C_SW_RESET") (class "Default")
      (node (ref "R33") (pin "2") (pinfunction "2_2") (pintype "passive"))
      (node (ref "T21") (pin "1") (pinfunction "G_1") (pintype "passive"))
    )
    (net (code "54") (name "/I2C_SW_RESET2") (class "Default")
      (node (ref "R46") (pin "2") (pinfunction "2_2") (pintype "passive"))
      (node (ref "T22") (pin "1") (pinfunction "G_1") (pintype "passive"))
    )
    (net (code "55") (name "/I2C_SW_RESET_N") (class "Default")
      (node (ref "IC14") (pin "24") (pinfunction "~{RESET}_24") (pintype "input"))
      (node (ref "IC15") (pin "24") (pinfunction "~{RESET}_24") (pintype "input"))
      (node (ref "R151") (pin "1") (pinfunction "1_1") (pintype "passive"))
      (node (ref "T21") (pin "3") (pinfunction "D_3") (pintype "passive"))
      (node (ref "T22") (pin "3") (pinfunction "D_3") (pintype "passive"))
    )
    (net (code "56") (name "/I2C_SW_SCL") (class "Default")
      (node (ref "IC13") (pin "3") (pinfunction "SCL1_3") (pintype "bidirectional"))
      (node (ref "R147") (pin "1") (pinfunction "1_1") (pintype "passive"))
      (node (ref "TP14") (pin "1") (pinfunction "1_1") (pintype "bidirectional"))
    )
    (net (code "57") (name "/I2C_SW_SDA") (class "Default")
      (node (ref "IC13") (pin "4") (pinfunction "SDA1_4") (pintype "bidirectional"))
      (node (ref "R146") (pin "1") (pinfunction "1_1") (pintype "passive"))
      (node (ref "TP13") (pin "1") (pinfunction "1_1") (pintype "bidirectional"))
    )
    (net (code "58") (name "/Main_DCXO_OE") (class "Default")
      (node (ref "IC24") (pin "28") (pinfunction "GPA7_28") (pintype "bidirectional"))
      (node (ref "IC28") (pin "11") (pinfunction "P0_7_11") (pintype "bidirectional"))
    )
    (net (code "59") (name "/SFP_0.LED") (class "Default")
      (node (ref "IC25") (pin "28") (pinfunction "GPA7_28") (pintype "bidirectional"))
      (node (ref "IC29") (pin "11") (pinfunction "P0_7_11") (pintype "bidirectional"))
    )
    (net (code "60") (name "/SFP_0.LOS") (class "Default")
      (node (ref "IC25") (pin "26") (pinfunction "GPA5_26") (pintype "bidirectional"))
      (node (ref "IC29") (pin "9") (pinfunction "P0_5_9") (pintype "bidirectional"))
    )
    (net (code "61") (name "/SFP_0.MOD_PRESENT") (class "Default")
      (node (ref "IC25") (pin "25") (pinfunction "GPA4_25") (pintype "bidirectional"))
      (node (ref "IC29") (pin "8") (pinfunction "P0_4_8") (pintype "bidirectional"))
    )
    (net (code "62") (name "/SFP_0.RATE_SELECT") (class "Default")
      (node (ref "IC25") (pin "24") (pinfunction "GPA3_24") (pintype "bidirectional"))
      (node (ref "IC29") (pin "7") (pinfunction "P0_3_7") (pintype "bidirectional"))
    )
    (net (code "63") (name "/SFP_0.RATE_SELECT1") (class "Default")
      (node (ref "IC25") (pin "23") (pinfunction "GPA2_23") (pintype "bidirectional"))
      (node (ref "IC29") (pin "6") (pinfunction "P0_2_6") (pintype "bidirectional"))
    )
    (net (code "64") (name "/SFP_0.SCL") (class "Default")
      (node (ref "IC15") (pin "2") (pinfunction "SC0_2") (pintype "bidirectional"))
      (node (ref "R184") (pin "1") (pinfunction "1_1") (pintype "passive"))
    )
    (net (code "65") (name "/SFP_0.SDA") (class "Default")
      (node (ref "IC15") (pin "1") (pinfunction "SD0_1") (pintype "bidirectional"))
      (node (ref "R183") (pin "1") (pinfunction "1_1") (pintype "passive"))
    )
    (net (code "66") (name "/SFP_0.TX_DISABLE") (class "Default")
      (node (ref "IC25") (pin "22") (pinfunction "GPA1_22") (pintype "bidirectional"))
      (node (ref "IC29") (pin "5") (pinfunction "P0_1_5") (pintype "bidirectional"))
    )
    (net (code "67") (name "/SFP_0.TX_FAULT") (class "Default")
      (node (ref "IC25") (pin "21") (pinfunction "GPA0_21") (pintype "bidirectional"))
      (node (ref "IC29") (pin "4") (pinfunction "P0_0_4") (pintype "bidirectional"))
    )
    (net (code "69") (name "/SFP_1.LED") (class "Default")
      (node (ref "IC25") (pin "7") (pinfunction "GPB6_7") (pintype "bidirectional"))
      (node (ref "IC29") (pin "19") (pinfunction "P1_6_19") (pintype "bidirectional"))
    )
    (net (code "70") (name "/SFP_1.LOS") (class "Default")
      (node (ref "IC25") (pin "6") (pinfunction "GPB5_6") (pintype "bidirectional"))
      (node (ref "IC29") (pin "18") (pinfunction "P1_5_18") (pintype "bidirectional"))
    )
    (net (code "71") (name "/SFP_1.MOD_PRESENT") (class "Default")
      (node (ref "IC25") (pin "5") (pinfunction "GPB4_5") (pintype "bidirectional"))
      (node (ref "IC29") (pin "17") (pinfunction "P1_4_17") (pintype "bidirectional"))
    )
    (net (code "72") (name "/SFP_1.RATE_SELECT") (class "Default")
      (node (ref "IC25") (pin "4") (pinfunction "GPB3_4") (pintype "bidirectional"))
      (node (ref "IC29") (pin "16") (pinfunction "P1_3_16") (pintype "bidirectional"))
    )
    (net (code "73") (name "/SFP_1.RATE_SELECT1") (class "Default")
      (node (ref "IC25") (pin "3") (pinfunction "GPB2_3") (pintype "bidirectional"))
      (node (ref "IC29") (pin "15") (pinfunction "P1_2_15") (pintype "bidirectional"))
    )
    (net (code "74") (name "/SFP_1.SCL") (class "Default")
      (node (ref "IC15") (pin "4") (pinfunction "SC1_4") (pintype "bidirectional"))
      (node (ref "R186") (pin "1") (pinfunction "1_1") (pintype "passive"))
    )
    (net (code "75") (name "/SFP_1.SDA") (class "Default")
      (node (ref "IC15") (pin "3") (pinfunction "SD1_3") (pintype "bidirectional"))
      (node (ref "R185") (pin "1") (pinfunction "1_1") (pintype "passive"))
    )
    (net (code "76") (name "/SFP_1.TX_DISABLE") (class "Default")
      (node (ref "IC25") (pin "2") (pinfunction "GPB1_2") (pintype "bidirectional"))
      (node (ref "IC29") (pin "14") (pinfunction "P1_1_14") (pintype "bidirectional"))
    )
    (net (code "77") (name "/SFP_1.TX_FAULT") (class "Default")
      (node (ref "IC25") (pin "1") (pinfunction "GPB0_1") (pintype "bidirectional"))
      (node (ref "IC29") (pin "13") (pinfunction "P1_0_13") (pintype "bidirectional"))
    )
    (net (code "79") (name "/SFP_2.LED") (class "Default")
      (node (ref "IC24") (pin "27") (pinfunction "GPA6_27") (pintype "bidirectional"))
      (node (ref "IC28") (pin "10") (pinfunction "P0_6_10") (pintype "bidirectional"))
    )
    (net (code "80") (name "/SFP_2.LOS") (class "Default")
      (node (ref "IC24") (pin "26") (pinfunction "GPA5_26") (pintype "bidirectional"))
      (node (ref "IC28") (pin "9") (pinfunction "P0_5_9") (pintype "bidirectional"))
    )
    (net (code "81") (name "/SFP_2.MOD_PRESENT") (class "Default")
      (node (ref "IC24") (pin "25") (pinfunction "GPA4_25") (pintype "bidirectional"))
      (node (ref "IC28") (pin "8") (pinfunction "P0_4_8") (pintype "bidirectional"))
    )
    (net (code "82") (name "/SFP_2.RATE_SELECT") (class "Default")
      (node (ref "IC24") (pin "24") (pinfunction "GPA3_24") (pintype "bidirectional"))
      (node (ref "IC28") (pin "7") (pinfunction "P0_3_7") (pintype "bidirectional"))
    )
    (net (code "83") (name "/SFP_2.RATE_SELECT1") (class "Default")
      (node (ref "IC24") (pin "23") (pinfunction "GPA2_23") (pintype "bidirectional"))
      (node (ref "IC28") (pin "6") (pinfunction "P0_2_6") (pintype "bidirectional"))
    )
    (net (code "84") (name "/SFP_2.SCL") (class "Default")
      (node (ref "IC15") (pin "6") (pinfunction "SC2_6") (pintype "bidirectional"))
      (node (ref "R188") (pin "1") (pinfunction "1_1") (pintype "passive"))
    )
    (net (code "85") (name "/SFP_2.SDA") (class "Default")
      (node (ref "IC15") (pin "5") (pinfunction "SD2_5") (pintype "bidirectional"))
      (node (ref "R187") (pin "1") (pinfunction "1_1") (pintype "passive"))
    )
    (net (code "86") (name "/SFP_2.TX_DISABLE") (class "Default")
      (node (ref "IC24") (pin "22") (pinfunction "GPA1_22") (pintype "bidirectional"))
      (node (ref "IC28") (pin "5") (pinfunction "P0_1_5") (pintype "bidirectional"))
    )
    (net (code "87") (name "/SFP_2.TX_FAULT") (class "Default")
      (node (ref "IC24") (pin "21") (pinfunction "GPA0_21") (pintype "bidirectional"))
      (node (ref "IC28") (pin "4") (pinfunction "P0_0_4") (pintype "bidirectional"))
    )
    (net (code "89") (name "/SFP_3.LED") (class "Default")
      (node (ref "IC24") (pin "8") (pinfunction "GPB7_8") (pintype "bidirectional"))
      (node (ref "IC28") (pin "20") (pinfunction "P1_7_20") (pintype "bidirectional"))
    )
    (net (code "90") (name "/SFP_3.LOS") (class "Default")
      (node (ref "IC24") (pin "6") (pinfunction "GPB5_6") (pintype "bidirectional"))
      (node (ref "IC28") (pin "18") (pinfunction "P1_5_18") (pintype "bidirectional"))
    )
    (net (code "91") (name "/SFP_3.MOD_PRESENT") (class "Default")
      (node (ref "IC24") (pin "5") (pinfunction "GPB4_5") (pintype "bidirectional"))
      (node (ref "IC28") (pin "17") (pinfunction "P1_4_17") (pintype "bidirectional"))
    )
    (net (code "92") (name "/SFP_3.RATE_SELECT") (class "Default")
      (node (ref "IC24") (pin "4") (pinfunction "GPB3_4") (pintype "bidirectional"))
      (node (ref "IC28") (pin "16") (pinfunction "P1_3_16") (pintype "bidirectional"))
    )
    (net (code "93") (name "/SFP_3.RATE_SELECT1") (class "Default")
      (node (ref "IC24") (pin "3") (pinfunction "GPB2_3") (pintype "bidirectional"))
      (node (ref "IC28") (pin "15") (pinfunction "P1_2_15") (pintype "bidirectional"))
    )
    (net (code "94") (name "/SFP_3.TX_DISABLE") (class "Default")
      (node (ref "IC24") (pin "2") (pinfunction "GPB1_2") (pintype "bidirectional"))
      (node (ref "IC28") (pin "14") (pinfunction "P1_1_14") (pintype "bidirectional"))
    )
    (net (code "95") (name "/SFP_3.TX_FAULT") (class "Default")
      (node (ref "IC24") (pin "1") (pinfunction "GPB0_1") (pintype "bidirectional"))
      (node (ref "IC28") (pin "13") (pinfunction "P1_0_13") (pintype "bidirectional"))
    )
    (net (code "97") (name "/SHARED_SCL") (class "Default")
      (node (ref "IC15") (pin "8") (pinfunction "SC3_8") (pintype "bidirectional"))
      (node (ref "R190") (pin "1") (pinfunction "1_1") (pintype "passive"))
      (node (ref "R228") (pin "1") (pinfunction "1_1") (pintype "passive"))
      (node (ref "R229") (pin "1") (pinfunction "1_1") (pintype "passive"))
      (node (ref "R231") (pin "1") (pinfunction "1_1") (pintype "passive"))
      (node (ref "R235") (pin "1") (pinfunction "1_1") (pintype "passive"))
      (node (ref "TP3") (pin "1") (pinfunction "1_1") (pintype "bidirectional"))
    )
    (net (code "98") (name "/SHARED_SDA") (class "Default")
      (node (ref "IC15") (pin "7") (pinfunction "SD3_7") (pintype "bidirectional"))
      (node (ref "R189") (pin "1") (pinfunction "1_1") (pintype "passive"))
      (node (ref "R230") (pin "1") (pinfunction "1_1") (pintype "passive"))
      (node (ref "R232") (pin "1") (pinfunction "1_1") (pintype "passive"))
      (node (ref "R233") (pin "1") (pinfunction "1_1") (pintype "passive"))
      (node (ref "R234") (pin "1") (pinfunction "1_1") (pintype "passive"))
      (node (ref "TP2") (pin "1") (pinfunction "1_1") (pintype "bidirectional"))
    )
    (net (code "99") (name "/VUSB_PRESENT_N") (class "Default")
      (node (ref "IC25") (pin "27") (pinfunction "GPA6_27") (pintype "bidirectional"))
      (node (ref "IC29") (pin "10") (pinfunction "P0_6_10") (pintype "bidirectional"))
    )
    (net (code "102") (name "GND") (class "Default")
      (node (ref "C186") (pin "1") (pinfunction "1_1") (pintype "passive"))
      (node (ref "C192") (pin "1") (pinfunction "1_1") (pintype "passive"))
      (node (ref "C193") (pin "1") (pinfunction "1_1") (pintype "passive"))
      (node (ref "C196") (pin "1") (pinfunction "1_1") (pintype "passive"))
      (node (ref "C197") (pin "1") (pinfunction "1_1") (pintype "passive"))
      (node (ref "C198") (pin "1") (pinfunction "1_1") (pintype "passive"))
      (node (ref "C203") (pin "1") (pinfunction "1_1") (pintype "passive"))
      (node (ref "C227") (pin "1") (pinfunction "1_1") (pintype "passive"))
      (node (ref "C305") (pin "1") (pinfunction "1_1") (pintype "passive"))
      (node (ref "C306") (pin "1") (pinfunction "1_1") (pintype "passive"))
      (node (ref "C307") (pin "1") (pinfunction "1_1") (pintype "passive"))
      (node (ref "IC13") (pin "1") (pinfunction "GND_1") (pintype "power_in"))
      (node (ref "IC14") (pin "18") (pinfunction "A2_18") (pintype "input"))
      (node (ref "IC14") (pin "22") (pinfunction "A0_22") (pintype "input"))
      (node (ref "IC14") (pin "23") (pinfunction "A1_23") (pintype "input"))
      (node (ref "IC14") (pin "25") (pinfunction "EP_25") (pintype "power_in"))
      (node (ref "IC14") (pin "9") (pinfunction "GND_9") (pintype "power_in"))
      (node (ref "IC15") (pin "18") (pinfunction "A2_18") (pintype "input"))
      (node (ref "IC15") (pin "23") (pinfunction "A1_23") (pintype "input"))
      (node (ref "IC15") (pin "25") (pinfunction "EP_25") (pintype "power_in"))
      (node (ref "IC15") (pin "9") (pinfunction "GND_9") (pintype "power_in"))
      (node (ref "IC24") (pin "10") (pinfunction "VSS_10") (pintype "power_in"))
      (node (ref "IC24") (pin "16") (pinfunction "A1_16") (pintype "input"))
      (node (ref "IC24") (pin "17") (pinfunction "A2_17") (pintype "input"))
      (node (ref "IC25") (pin "10") (pinfunction "VSS_10") (pintype "power_in"))
      (node (ref "IC25") (pin "15") (pinfunction "A0_15") (pintype "input"))
      (node (ref "IC25") (pin "16") (pinfunction "A1_16") (pintype "input"))
      (node (ref "IC25") (pin "17") (pinfunction "A2_17") (pintype "input"))
      (node (ref "IC28") (pin "12") (pinfunction "GND_12") (pintype "power_in"))
      (node (ref "IC28") (pin "2") (pinfunction "A1_2") (pintype "input"))
      (node (ref "IC29") (pin "12") (pinfunction "GND_12") (pintype "power_in"))
      (node (ref "IC29") (pin "2") (pinfunction "A1_2") (pintype "input"))
      (node (ref "IC29") (pin "21") (pinfunction "A0_21") (pintype "input"))
      (node (ref "IC30") (pin "2") (pinfunction "VSS_2") (pintype "power_in"))
      (node (ref "IC30") (pin "4") (pinfunction "A1_4") (pintype "input"))
      (node (ref "IC30") (pin "5") (pinfunction "A0_5") (pintype "input"))
      (node (ref "IC31") (pin "1") (pinfunction "A0_1") (pintype "input"))
      (node (ref "IC31") (pin "2") (pinfunction "A1_2") (pintype "input"))
      (node (ref "IC31") (pin "3") (pinfunction "A2_3") (pintype "input"))
      (node (ref "IC31") (pin "4") (pinfunction "VSS_4") (pintype "power_in"))
      (node (ref "IC5") (pin "4") (pinfunction "VSS_4") (pintype "power_in"))
      (node (ref "R269") (pin "2") (pinfunction "2_2") (pintype "passive"))
      (node (ref "R270") (pin "2") (pinfunction "2_2") (pintype "passive"))
      (node (ref "R272") (pin "1") (pinfunction "1_1") (pintype "passive"))
      (node (ref "R33") (pin "1") (pinfunction "1_1") (pintype "passive"))
      (node (ref "R46") (pin "1") (pinfunction "1_1") (pintype "passive"))
      (node (ref "T21") (pin "2") (pinfunction "S_2") (pintype "passive"))
      (node (ref "T22") (pin "2") (pinfunction "S_2") (pintype "passive"))
    )
    (net (code "103") (name "Net-(IC5-SCL)") (class "Default")
      (node (ref "IC5") (pin "6") (pinfunction "SCL_6") (pintype "input"))
      (node (ref "R231") (pin "2") (pinfunction "2_2") (pintype "passive"))
    )
    (net (code "104") (name "Net-(IC5-SDA)") (class "Default")
      (node (ref "IC5") (pin "5") (pinfunction "SDA_5") (pintype "bidirectional"))
      (node (ref "R230") (pin "2") (pinfunction "2_2") (pintype "passive"))
    )
    (net (code "105") (name "Net-(IC13-EN)") (class "Default")
      (node (ref "C186") (pin "2") (pinfunction "2_2") (pintype "passive"))
      (node (ref "IC13") (pin "7") (pinfunction "VREF2_7") (pintype "input"))
      (node (ref "IC13") (pin "8") (pinfunction "EN_8") (pintype "input"))
      (node (ref "R240") (pin "1") (pinfunction "1_1") (pintype "passive"))
    )
    (net (code "106") (name "P2V5") (class "Default")
      (node (ref "C193") (pin "2") (pinfunction "2_2") (pintype "passive"))
      (node (ref "C307") (pin "2") (pinfunction "2_2") (pintype "passive"))
      (node (ref "IC13") (pin "2") (pinfunction "VREF1_2") (pintype "input"))
      (node (ref "IC30") (pin "6") (pinfunction "VCC_6") (pintype "power_in"))
      (node (ref "IC31") (pin "8") (pinfunction "VCC_8") (pintype "power_in"))
      (node (ref "R146") (pin "2") (pinfunction "2_2") (pintype "passive"))
      (node (ref "R147") (pin "2") (pinfunction "2_2") (pintype "passive"))
      (node (ref "R264") (pin "2") (pinfunction "2_2") (pintype "passive"))
      (node (ref "R265") (pin "2") (pinfunction "2_2") (pintype "passive"))
      (node (ref "R267") (pin "2") (pinfunction "2_2") (pintype "passive"))
      (node (ref "R268") (pin "2") (pinfunction "2_2") (pintype "passive"))
      (node (ref "R271") (pin "2") (pinfunction "2_2") (pintype "passive"))
    )
    (net (code "107") (name "P3V3") (class "Default")
      (node (ref "C192") (pin "2") (pinfunction "2_2") (pintype "passive"))
      (node (ref "C196") (pin "2") (pinfunction "2_2") (pintype "passive"))
      (node (ref "C197") (pin "2") (pinfunction "2_2") (pintype "passive"))
      (node (ref "C198") (pin "2") (pinfunction "2_2") (pintype "passive"))
      (node (ref "C203") (pin "2") (pinfunction "2_2") (pintype "passive"))
      (node (ref "C227") (pin "2") (pinfunction "2_2") (pintype "passive"))
      (node (ref "C305") (pin "2") (pinfunction "2_2") (pintype "passive"))
      (node (ref "C306") (pin "2") (pinfunction "2_2") (pintype "passive"))
      (node (ref "IC14") (pin "21") (pinfunction "VCC_21") (pintype "power_in"))
      (node (ref "IC15") (pin "21") (pinfunction "VCC_21") (pintype "power_in"))
      (node (ref "IC15") (pin "22") (pinfunction "A0_22") (pintype "input"))
      (node (ref "IC24") (pin "15") (pinfunction "A0_15") (pintype "input"))
      (node (ref "IC24") (pin "9") (pinfunction "VDD_9") (pintype "power_in"))
      (node (ref "IC25") (pin "9") (pinfunction "VDD_9") (pintype "power_in"))
      (node (ref "IC28") (pin "21") (pinfunction "A0_21") (pintype "input"))
      (node (ref "IC28") (pin "24") (pinfunction "VCC_24") (pintype "power_in"))
      (node (ref "IC29") (pin "24") (pinfunction "VCC_24") (pintype "power_in"))
      (node (ref "IC5") (pin "1") (pinfunction "A0_1") (pintype "input"))
      (node (ref "IC5") (pin "2") (pinfunction "A1_2") (pintype "input"))
      (node (ref "IC5") (pin "3") (pinfunction "A2_3") (pintype "input"))
      (node (ref "IC5") (pin "8") (pinfunction "VCC_8") (pintype "power_in"))
      (node (ref "R131") (pin "1") (pinfunction "1_1") (pintype "passive"))
      (node (ref "R132") (pin "1") (pinfunction "1_1") (pintype "passive"))
      (node (ref "R148") (pin "2") (pinfunction "2_2") (pintype "passive"))
      (node (ref "R149") (pin "2") (pinfunction "2_2") (pintype "passive"))
      (node (ref "R151") (pin "2") (pinfunction "2_2") (pintype "passive"))
      (node (ref "R155") (pin "2") (pinfunction "2_2") (pintype "passive"))
      (node (ref "R156") (pin "2") (pinfunction "2_2") (pintype "passive"))
      (node (ref "R157") (pin "2") (pinfunction "2_2") (pintype "passive"))
      (node (ref "R158") (pin "2") (pinfunction "2_2") (pintype "passive"))
      (node (ref "R159") (pin "2") (pinfunction "2_2") (pintype "passive"))
      (node (ref "R160") (pin "2") (pinfunction "2_2") (pintype "passive"))
      (node (ref "R161") (pin "2") (pinfunction "2_2") (pintype "passive"))
      (node (ref "R162") (pin "2") (pinfunction "2_2") (pintype "passive"))
      (node (ref "R163") (pin "2") (pinfunction "2_2") (pintype "passive"))
      (node (ref "R164") (pin "2") (pinfunction "2_2") (pintype "passive"))
      (node (ref "R165") (pin "2") (pinfunction "2_2") (pintype "passive"))
      (node (ref "R166") (pin "2") (pinfunction "2_2") (pintype "passive"))
      (node (ref "R167") (pin "2") (pinfunction "2_2") (pintype "passive"))
      (node (ref "R168") (pin "2") (pinfunction "2_2") (pintype "passive"))
      (node (ref "R169") (pin "2") (pinfunction "2_2") (pintype "passive"))
      (node (ref "R170") (pin "2") (pinfunction "2_2") (pintype "passive"))
      (node (ref "R171") (pin "2") (pinfunction "2_2") (pintype "passive"))
      (node (ref "R172") (pin "2") (pinfunction "2_2") (pintype "passive"))
      (node (ref "R173") (pin "2") (pinfunction "2_2") (pintype "passive"))
      (node (ref "R175") (pin "2") (pinfunction "2_2") (pintype "passive"))
      (node (ref "R176") (pin "2") (pinfunction "2_2") (pintype "passive"))
      (node (ref "R178") (pin "2") (pinfunction "2_2") (pintype "passive"))
      (node (ref "R180") (pin "2") (pinfunction "2_2") (pintype "passive"))
      (node (ref "R182") (pin "2") (pinfunction "2_2") (pintype "passive"))
      (node (ref "R183") (pin "2") (pinfunction "2_2") (pintype "passive"))
      (node (ref "R184") (pin "2") (pinfunction "2_2") (pintype "passive"))
      (node (ref "R185") (pin "2") (pinfunction "2_2") (pintype "passive"))
      (node (ref "R186") (pin "2") (pinfunction "2_2") (pintype "passive"))
      (node (ref "R187") (pin "2") (pinfunction "2_2") (pintype "passive"))
      (node (ref "R188") (pin "2") (pinfunction "2_2") (pintype "passive"))
      (node (ref "R189") (pin "2") (pinfunction "2_2") (pintype "passive"))
      (node (ref "R190") (pin "2") (pinfunction "2_2") (pintype "passive"))
      (node (ref "R240") (pin "2") (pinfunction "2_2") (pintype "passive"))
    )
    (net (code "108") (name "unconnected-(IC5-NC-Pad7)") (class "Default")
      (node (ref "IC5") (pin "7") (pinfunction "NC_7") (pintype "passive+no_connect"))
    )
    (net (code "109") (name "unconnected-(IC24-INTB-Pad19)") (class "Default")
      (node (ref "IC24") (pin "19") (pinfunction "INTB_19") (pintype "output+no_connect"))
    )
    (net (code "110") (name "unconnected-(IC24-NC-Pad11)") (class "Default")
      (node (ref "IC24") (pin "11") (pinfunction "NC_11") (pintype "passive+no_connect"))
    )
    (net (code "111") (name "unconnected-(IC24-NC-Pad14)") (class "Default")
      (node (ref "IC24") (pin "14") (pinfunction "NC_14") (pintype "passive+no_connect"))
    )
    (net (code "112") (name "unconnected-(IC25-INTB-Pad19)") (class "Default")
      (node (ref "IC25") (pin "19") (pinfunction "INTB_19") (pintype "output+no_connect"))
    )
    (net (code "113") (name "unconnected-(IC25-NC-Pad11)") (class "Default")
      (node (ref "IC25") (pin "11") (pinfunction "NC_11") (pintype "passive+no_connect"))
    )
    (net (code "114") (name "unconnected-(IC25-NC-Pad14)") (class "Default")
      (node (ref "IC25") (pin "14") (pinfunction "NC_14") (pintype "passive+no_connect"))
    )
    (net (code "115") (name "unconnected-(IC31-NC-Pad7)") (class "Default")
      (node (ref "IC31") (pin "7") (pinfunction "NC_7") (pintype "passive+no_connect"))
    )
    (net (code "116") (name "unconnected-(R234-Pad2)") (class "Default")
      (node (ref "R234") (pin "2") (pinfunction "2_2") (pintype "passive"))
    )
    (net (code "117") (name "unconnected-(R235-Pad2)") (class "Default")
      (node (ref "R235") (pin "2") (pinfunction "2_2") (pintype "passive"))
    )
  )
)
